# Booster_Board.net
KiCad netlist of a schematic drawn in Altium Designer
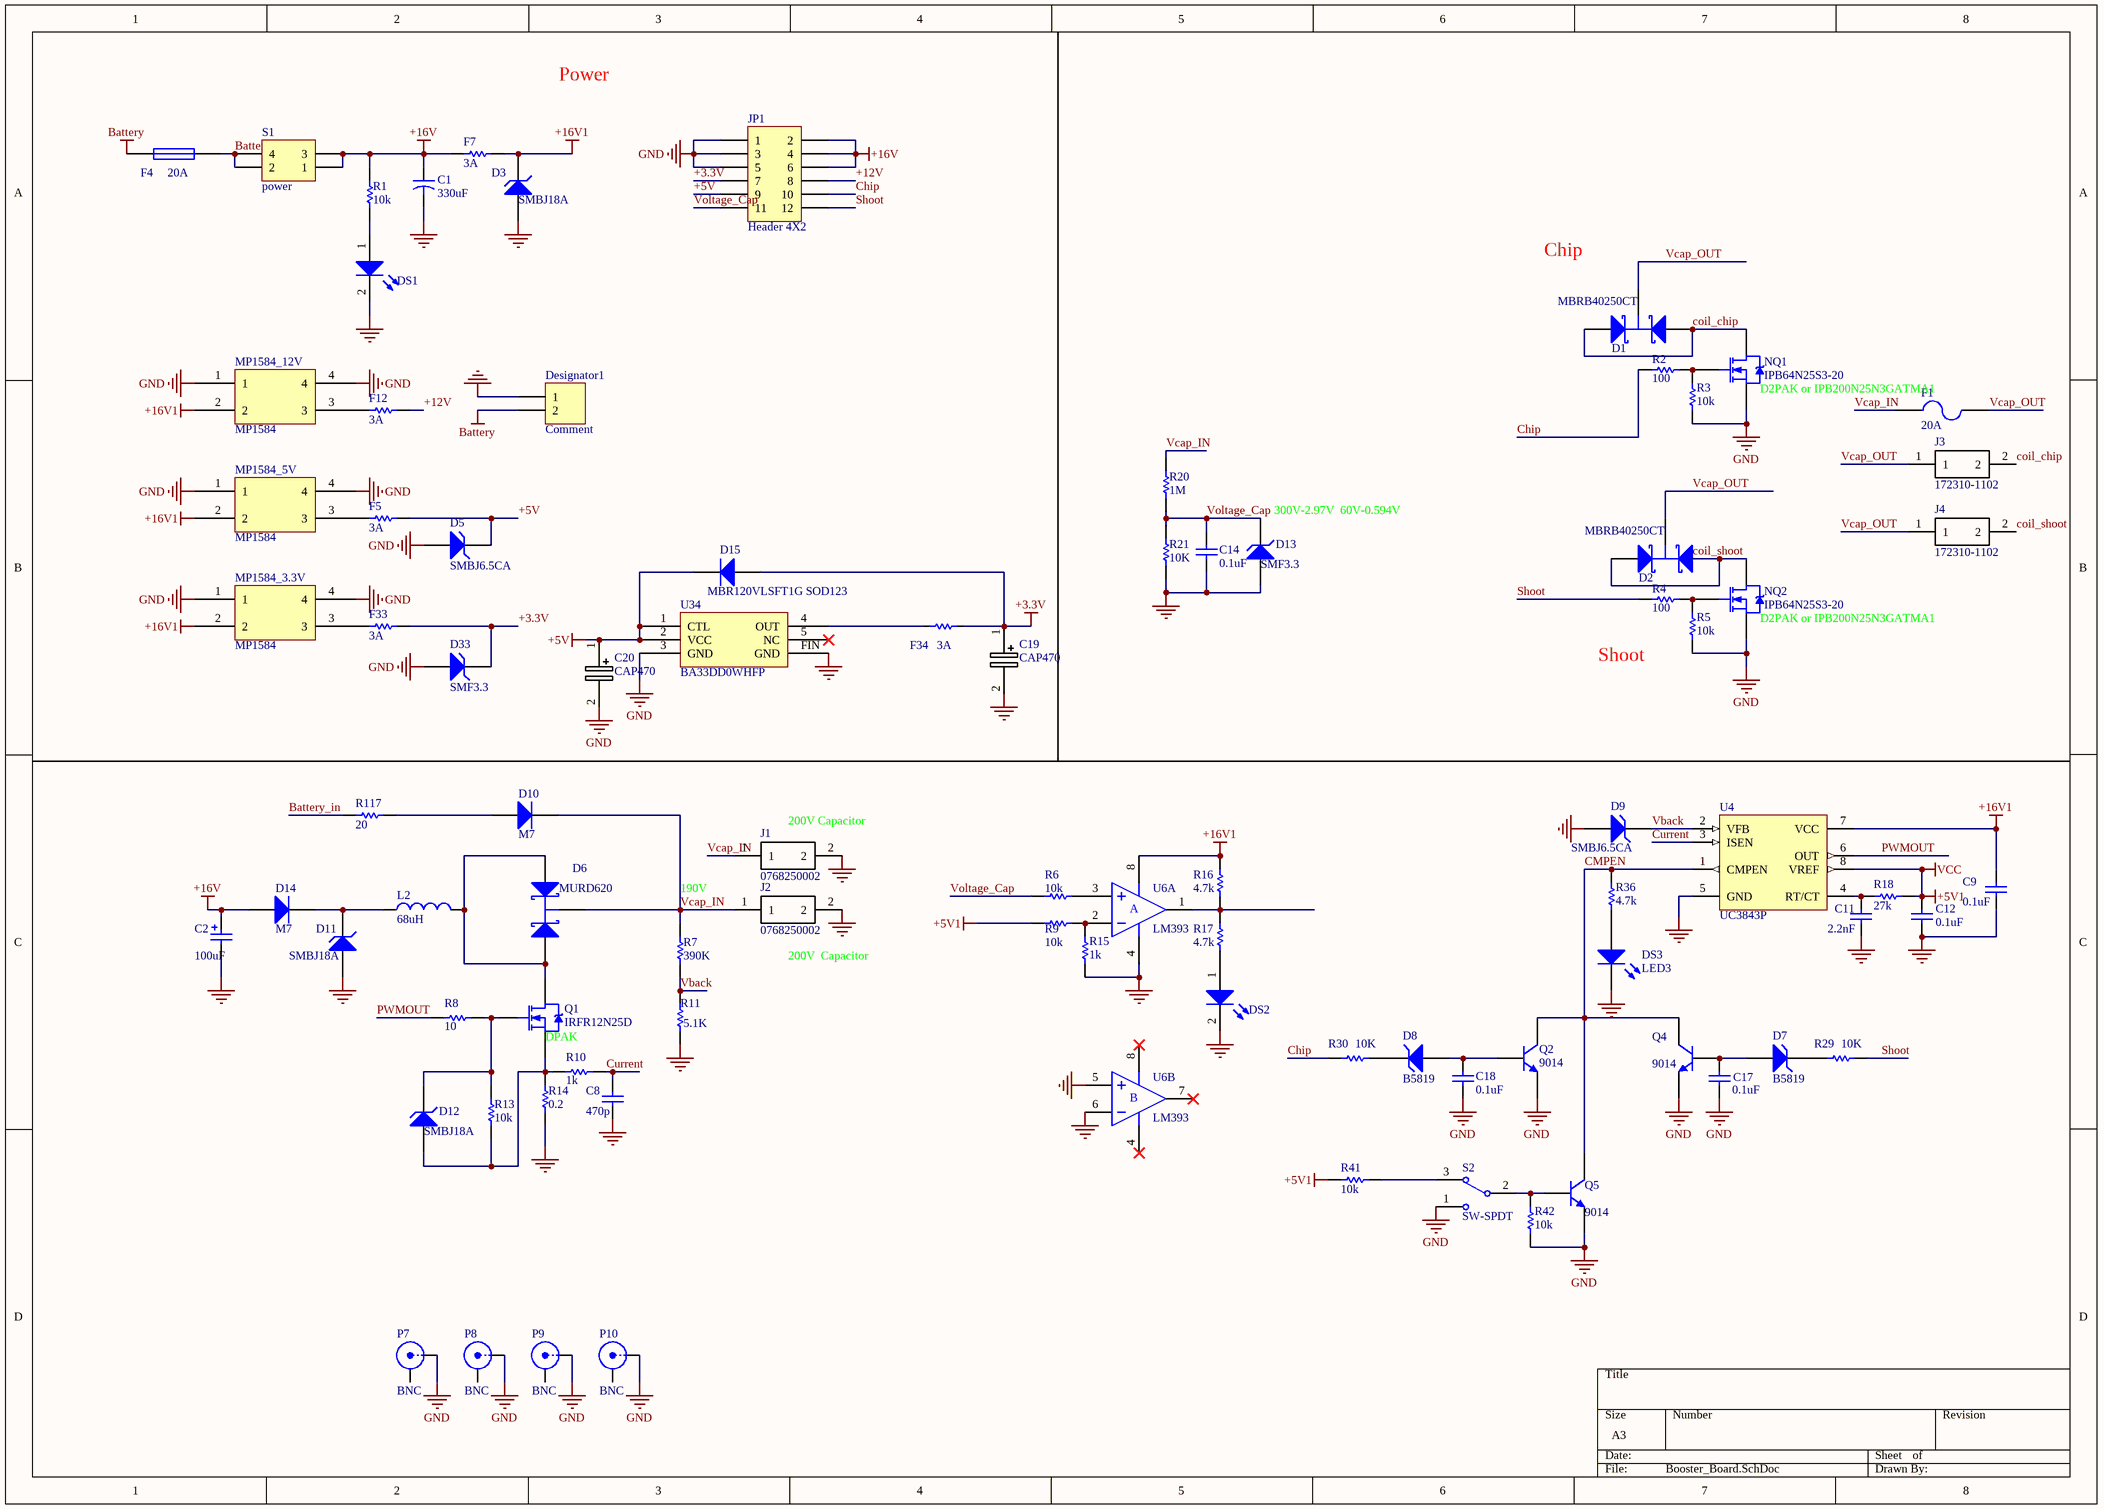
[diagram p0: Booster_Board.SchDoc]

(export (version "E")
  (design (tool "Eeschema 10.0.6"))
  (components
    (comp (ref "C1")
      (value "330uF")
      (footprint "470uF")
      (description "Capacitor")
      (fields (field (name "PUBLISHER") "Altium Limited"))
      (libsource (lib "Miscellaneous Devices") (part "Cap2"))
    )
    (comp (ref "C2")
      (value "100uF")
      (footprint "100uF")
      (description "Polarized Capacitor (Radial)")
      (fields
        (field (name "MANUFACTURER") "Generic Components")
        (field (name "Comment") "100uf")
        (field (name "PUBLISHER") "Altium Hobart Technology Centre")
      )
      (libsource (lib "Miscellaneous Devices") (part "Cap Pol1"))
    )
    (comp (ref "C8")
      (value "470p")
      (footprint "0805C")
      (description "Capacitor")
      (fields
        (field (name "MANUFACTURER") "Generic Components")
        (field (name "PUBLISHER") "Altium Hobart Technology Centre")
      )
      (libsource (lib "Miscellaneous Devices") (part "Cap"))
    )
    (comp (ref "C9")
      (value "0.1uF")
      (footprint "0805C")
      (description "Capacitor")
      (fields (field (name "PUBLISHER") "Altium Limited"))
      (libsource (lib "Miscellaneous Devices") (part "Cap"))
    )
    (comp (ref "C11")
      (value "2.2nF")
      (footprint "0805C")
      (description "Capacitor")
      (fields
        (field (name "MANUFACTURER") "Generic Components")
        (field (name "Comment") "2.2nf")
        (field (name "PUBLISHER") "Altium Hobart Technology Centre")
      )
      (libsource (lib "Miscellaneous Devices") (part "Cap"))
    )
    (comp (ref "C12")
      (value "0.1uF")
      (footprint "0805C")
      (description "Capacitor")
      (fields
        (field (name "MANUFACTURER") "Generic Components")
        (field (name "PUBLISHER") "Altium Hobart Technology Centre")
      )
      (libsource (lib "Miscellaneous Devices") (part "Cap"))
    )
    (comp (ref "C14")
      (value "0.1uF")
      (footprint "0805C")
      (description "Capacitor")
      (fields (field (name "PUBLISHER") "Altium Limited"))
      (libsource (lib "Miscellaneous Devices") (part "Cap"))
    )
    (comp (ref "C17")
      (value "0.1uF")
      (footprint "0805c")
      (description "Capacitor")
      (fields (field (name "PUBLISHER") "Altium Limited"))
      (libsource (lib "Miscellaneous Devices") (part "Cap"))
    )
    (comp (ref "C18")
      (value "0.1uF")
      (footprint "0805c")
      (description "Capacitor")
      (fields (field (name "PUBLISHER") "Altium Limited"))
      (libsource (lib "Miscellaneous Devices") (part "Cap"))
    )
    (comp (ref "C19")
      (value "CAP470")
      (footprint "Main_Board:CAPPM7360X200N")
      (description "470uF电容贴片")
      (fields
        (field (name "MANUFACTURER_PART_NUMBER") "T523H477M016APE0707280")
        (field (name "MOUSER PART NUMBER") "80-T523H477M16P070LR")
      )
      (libsource (lib "Main_Board") (part "T523H477M016APE0707280"))
    )
    (comp (ref "C20")
      (value "CAP470")
      (footprint "Main_Board:CAPPM7360X200N")
      (description "470uF电容贴片")
      (fields
        (field (name "MANUFACTURER_PART_NUMBER") "T523H477M016APE0707280")
        (field (name "MOUSER PART NUMBER") "80-T523H477M16P070LR")
      )
      (libsource (lib "Main_Board") (part "T523H477M016APE0707280"))
    )
    (comp (ref "D1")
      (value "MBRB40250CT")
      (footprint "D2PAK")
      (description "Schottky Rectifier")
      (fields
        (field (name "MANUFACTURER") "International Rectifier")
        (field (name "PUBLISHER") "Altium Hobart Technology Centre")
      )
      (libsource (lib "IR Discrete Diode") (part "MBRB1545CT"))
    )
    (comp (ref "D2")
      (value "MBRB40250CT")
      (footprint "D2PAK")
      (description "Schottky Rectifier")
      (fields
        (field (name "MANUFACTURER") "International Rectifier")
        (field (name "PUBLISHER") "Altium Hobart Technology Centre")
      )
      (libsource (lib "IR Discrete Diode") (part "MBRB1545CT"))
    )
    (comp (ref "D3")
      (value "SMBJ18A")
      (footprint "booster:SMBJ6.5")
      (description "Zener Diode")
      (fields (field (name "PUBLISHER") "Altium Limited"))
      (libsource (lib "Miscellaneous Devices") (part "D Zener"))
    )
    (comp (ref "D5")
      (value "SMBJ6.5CA")
      (footprint "SMBJ6.5")
      (description "Zener Diode")
      (fields (field (name "PUBLISHER") "Altium Limited"))
      (libsource (lib "Miscellaneous Devices") (part "D Zener"))
    )
    (comp (ref "D6")
      (value "MURD620")
      (footprint "DPAK")
      (description "Schottky Rectifier")
      (fields
        (field (name "MANUFACTURER") "International Rectifier")
        (field (name "PUBLISHER") "Altium Hobart Technology Centre")
      )
      (libsource (lib "IR Discrete Diode") (part "MBRB1545CT"))
    )
    (comp (ref "D7")
      (value "B5819")
      (footprint "sod-123")
      (description "Zener Diode")
      (fields (field (name "PUBLISHER") "Altium Limited"))
      (libsource (lib "Miscellaneous Devices") (part "D Zener"))
    )
    (comp (ref "D8")
      (value "B5819")
      (footprint "sod-123")
      (description "Zener Diode")
      (fields (field (name "PUBLISHER") "Altium Limited"))
      (libsource (lib "Miscellaneous Devices") (part "D Zener"))
    )
    (comp (ref "D9")
      (value "SMBJ6.5CA")
      (footprint "SMBJ6.5")
      (description "Zener Diode")
      (fields (field (name "PUBLISHER") "Altium Limited"))
      (libsource (lib "Miscellaneous Devices") (part "D Zener"))
    )
    (comp (ref "D10")
      (value "M7")
      (footprint "booster:SMA")
      (description "Default Diode")
      (fields
        (field (name "MANUFACTURER") "Generic Components")
        (field (name "PUBLISHER") "Altium Hobart Technology Centre")
      )
      (libsource (lib "Miscellaneous Devices") (part "Diode"))
    )
    (comp (ref "D11")
      (value "SMBJ18A")
      (footprint "booster:SMBJ6.5")
      (description "Zener Diode")
      (fields (field (name "PUBLISHER") "Altium Limited"))
      (libsource (lib "Miscellaneous Devices") (part "D Zener"))
    )
    (comp (ref "D12")
      (value "SMBJ18A")
      (footprint "SMBJ6.5")
      (description "Zener Diode")
      (fields (field (name "PUBLISHER") "Altium Limited"))
      (libsource (lib "Miscellaneous Devices") (part "D Zener"))
    )
    (comp (ref "D13")
      (value "SMF3.3")
      (footprint "SMF33")
      (description "Zener Diode")
      (fields (field (name "PUBLISHER") "Altium Limited"))
      (libsource (lib "Miscellaneous Devices") (part "D Zener"))
    )
    (comp (ref "D14")
      (value "M7")
      (footprint "booster:SMA")
      (description "Default Diode")
      (fields
        (field (name "MANUFACTURER") "Generic Components")
        (field (name "PUBLISHER") "Altium Hobart Technology Centre")
      )
      (libsource (lib "Miscellaneous Devices") (part "Diode"))
    )
    (comp (ref "D15")
      (value "MBR120VLSFT1G SOD123")
      (footprint "Main_Board:sod123")
      (description "Default Diode")
      (fields
        (field (name "MANUFACTURER") "Generic Components")
        (field (name "PUBLISHER") "Altium Hobart Technology Centre")
      )
      (libsource (lib "Miscellaneous Devices") (part "Diode"))
    )
    (comp (ref "D33")
      (value "SMF3.3")
      (footprint "SMF33")
      (description "Zener Diode")
      (fields (field (name "PUBLISHER") "Altium Limited"))
      (libsource (lib "Miscellaneous Devices") (part "D Zener"))
    )
    (comp (ref "Designator1")
      (value "Comment")
      (footprint "XT60PW")
      (description "Header, 2-Pin")
      (fields (field (name "PUBLISHER") "Altium Limited"))
      (libsource (lib "Miscellaneous Connectors") (part "Header 2"))
    )
    (comp (ref "DS1")
      (value "LED2")
      (footprint "0805A")
      (description "Typical RED, GREEN, YELLOW, AMBER GaAs LED")
      (fields
        (field (name "MANUFACTURER") "Generic Components")
        (field (name "PUBLISHER") "Altium Hobart Technology Centre")
      )
      (libsource (lib "") (part "LED2_1"))
    )
    (comp (ref "DS2")
      (value "LED2")
      (footprint "0805A")
      (description "Typical RED, GREEN, YELLOW, AMBER GaAs LED")
      (fields
        (field (name "MANUFACTURER") "Generic Components")
        (field (name "PUBLISHER") "Altium Hobart Technology Centre")
      )
      (libsource (lib "") (part "LED2_1"))
    )
    (comp (ref "DS3")
      (value "LED3")
      (footprint "booster:0805A")
      (description "Typical RED, GREEN, YELLOW, AMBER GaAs LED")
      (fields (field (name "PUBLISHER") "Altium Limited"))
      (libsource (lib "Miscellaneous Devices") (part "LED2"))
    )
    (comp (ref "F1")
      (value "20A")
      (footprint "20A")
      (fields (field (name "PUBLISHER") "Altium Limited"))
      (libsource (lib "Miscellaneous Devices") (part "Fuse 2"))
    )
    (comp (ref "F4")
      (value "20A")
      (footprint "20A")
      (description "Fuse")
      (fields (field (name "PUBLISHER") "Altium Limited"))
      (libsource (lib "Miscellaneous Devices") (part "Fuse 1"))
    )
    (comp (ref "F5")
      (value "3A")
      (footprint "2512r")
      (description "Resistor")
      (fields
        (field (name "MANUFACTURER") "Generic Components")
        (field (name "PUBLISHER") "Altium Hobart Technology Centre")
      )
      (libsource (lib "Miscellaneous Devices") (part "Res1"))
    )
    (comp (ref "F7")
      (value "3A")
      (footprint "2512r")
      (description "Resistor")
      (fields
        (field (name "MANUFACTURER") "Generic Components")
        (field (name "PUBLISHER") "Altium Hobart Technology Centre")
      )
      (libsource (lib "Miscellaneous Devices") (part "Res1"))
    )
    (comp (ref "F12")
      (value "3A")
      (footprint "2512r")
      (description "Resistor")
      (fields
        (field (name "MANUFACTURER") "Generic Components")
        (field (name "PUBLISHER") "Altium Hobart Technology Centre")
      )
      (libsource (lib "Miscellaneous Devices") (part "Res1"))
    )
    (comp (ref "F33")
      (value "3A")
      (footprint "2512r")
      (description "Resistor")
      (fields
        (field (name "MANUFACTURER") "Generic Components")
        (field (name "PUBLISHER") "Altium Hobart Technology Centre")
      )
      (libsource (lib "Miscellaneous Devices") (part "Res1"))
    )
    (comp (ref "F34")
      (value "3A")
      (footprint "2512r")
      (description "Resistor")
      (fields (field (name "PUBLISHER") "Altium Limited"))
      (libsource (lib "") (part "Res1_1"))
    )
    (comp (ref "J1")
      (value "0768250002")
      (footprint "booster:0768250002_version2")
      (description "Connector")
      (libsource (lib "booster") (part "0768250002"))
    )
    (comp (ref "J2")
      (value "0768250002")
      (footprint "booster:0768250002_version2")
      (description "Connector")
      (libsource (lib "booster") (part "0768250002"))
    )
    (comp (ref "J3")
      (value "172310-1102")
      (footprint "booster:172310-1102_VERSION2")
      (description "Connector")
      (fields (field (name "MOUSER PART NUMBER") "538-172310-1102") (field (name "RS PART NUMBER") "8951880"))
      (libsource (lib "booster") (part "172310-1102"))
    )
    (comp (ref "J4")
      (value "172310-1102")
      (footprint "booster:172310-1102_VERSION2")
      (description "Connector")
      (fields (field (name "MOUSER PART NUMBER") "538-172310-1102") (field (name "RS PART NUMBER") "8951880"))
      (libsource (lib "booster") (part "172310-1102"))
    )
    (comp (ref "JP1")
      (value "Header 4X2")
      (footprint "2*6_2.5mm")
      (description "Header, 4-Pin, Dual row")
      (fields (field (name "PUBLISHER") "Altium Limited"))
      (libsource (lib "booster") (part "Header 6X2"))
    )
    (comp (ref "L2")
      (value "68uH")
      (footprint "INDPM120120X1020N")
      (description "Inductor")
      (fields (field (name "PUBLISHER") "Altium Limited"))
      (libsource (lib "Miscellaneous Devices") (part "Inductor"))
    )
    (comp (ref "MP1584_3.3V") (value "MP1584") (footprint "1584") (libsource (lib "booster") (part "MP1584")))
    (comp (ref "MP1584_5V") (value "MP1584") (footprint "1584") (libsource (lib "booster") (part "MP1584")))
    (comp (ref "MP1584_12V") (value "MP1584") (footprint "1584") (libsource (lib "booster") (part "MP1584")))
    (comp (ref "NQ1")
      (value "IPB64N25S3-20")
      (footprint "D2PAK")
      (description "HEXFET Power MOSFET")
      (fields
        (field (name "MANUFACTURER") "International Rectifier")
        (field (name "PUBLISHER") "Altium Hobart Technology Centre")
      )
      (libsource (lib "IR Discrete MOSFET") (part "IRFP460"))
    )
    (comp (ref "NQ2")
      (value "IPB64N25S3-20")
      (footprint "D2PAK")
      (description "HEXFET Power MOSFET")
      (fields
        (field (name "MANUFACTURER") "International Rectifier")
        (field (name "PUBLISHER") "Altium Hobart Technology Centre")
      )
      (libsource (lib "IR Discrete MOSFET") (part "IRFP460"))
    )
    (comp (ref "P7")
      (value "BNC")
      (footprint "hole")
      (description "BNC Elbow Connector")
      (fields (field (name "PUBLISHER") "Altium Limited"))
      (libsource (lib "Miscellaneous Connectors") (part "BNC"))
    )
    (comp (ref "P8")
      (value "BNC")
      (footprint "hole")
      (description "BNC Elbow Connector")
      (fields (field (name "PUBLISHER") "Altium Limited"))
      (libsource (lib "Miscellaneous Connectors") (part "BNC"))
    )
    (comp (ref "P9")
      (value "BNC")
      (footprint "hole")
      (description "BNC Elbow Connector")
      (fields (field (name "PUBLISHER") "Altium Limited"))
      (libsource (lib "Miscellaneous Connectors") (part "BNC"))
    )
    (comp (ref "P10")
      (value "BNC")
      (footprint "hole")
      (description "BNC Elbow Connector")
      (fields (field (name "PUBLISHER") "Altium Limited"))
      (libsource (lib "Miscellaneous Connectors") (part "BNC"))
    )
    (comp (ref "Q1")
      (value "IRFR12N25D")
      (footprint "DPAK")
      (description "N-Channel Power MOSFET")
      (fields (field (name "PUBLISHER") "Altium Limited"))
      (libsource (lib "Miscellaneous Devices") (part "NMOS-2"))
    )
    (comp (ref "Q2")
      (value "9014")
      (footprint "元器件:SOT23A")
      (description "NPN General Purpose Amplifier")
      (fields
        (field (name "MANUFACTURER") "Fairchild Semiconductor")
        (field (name "PUBLISHER") "Altium Hobart Technology Centre")
      )
      (libsource (lib "FSC Discrete BJT") (part "BC817-40"))
    )
    (comp (ref "Q4")
      (value "9014")
      (footprint "sot23a")
      (description "NPN General Purpose Amplifier")
      (fields
        (field (name "MANUFACTURER") "Fairchild Semiconductor")
        (field (name "PUBLISHER") "Altium Hobart Technology Centre")
      )
      (libsource (lib "FSC Discrete BJT") (part "BC817-40"))
    )
    (comp (ref "Q5")
      (value "9014")
      (footprint "SOT23a")
      (description "NPN General Purpose Amplifier")
      (fields
        (field (name "MANUFACTURER") "Fairchild Semiconductor")
        (field (name "PUBLISHER") "Altium Hobart Technology Centre")
      )
      (libsource (lib "FSC Discrete BJT") (part "BC817-40"))
    )
    (comp (ref "R1")
      (value "10k")
      (footprint "0805R")
      (description "Resistor")
      (fields
        (field (name "MANUFACTURER") "Generic Components")
        (field (name "PUBLISHER") "Altium Hobart Technology Centre")
      )
      (libsource (lib "Miscellaneous Devices") (part "Res1"))
    )
    (comp (ref "R2")
      (value "100")
      (footprint "0805r")
      (description "Semiconductor Resistor")
      (fields
        (field (name "MANUFACTURER") "Generic Components")
        (field (name "PUBLISHER") "Altium Hobart Technology Centre")
      )
      (libsource (lib "Miscellaneous Devices") (part "Res Semi"))
    )
    (comp (ref "R3")
      (value "10k")
      (footprint "0805R")
      (description "Semiconductor Resistor")
      (fields
        (field (name "MANUFACTURER") "Generic Components")
        (field (name "PUBLISHER") "Altium Hobart Technology Centre")
      )
      (libsource (lib "Miscellaneous Devices") (part "Res Semi"))
    )
    (comp (ref "R4")
      (value "100")
      (footprint "0805r")
      (description "Semiconductor Resistor")
      (fields
        (field (name "MANUFACTURER") "Generic Components")
        (field (name "PUBLISHER") "Altium Hobart Technology Centre")
      )
      (libsource (lib "Miscellaneous Devices") (part "Res Semi"))
    )
    (comp (ref "R5")
      (value "10k")
      (footprint "0805R")
      (description "Semiconductor Resistor")
      (fields
        (field (name "MANUFACTURER") "Generic Components")
        (field (name "PUBLISHER") "Altium Hobart Technology Centre")
      )
      (libsource (lib "Miscellaneous Devices") (part "Res Semi"))
    )
    (comp (ref "R6")
      (value "10k")
      (footprint "0805R")
      (description "Resistor")
      (fields
        (field (name "MANUFACTURER") "Generic Components")
        (field (name "PUBLISHER") "Altium Hobart Technology Centre")
      )
      (libsource (lib "HAIBAO_MEGAV1.0_1") (part "Res1"))
    )
    (comp (ref "R7")
      (value "390K")
      (footprint "0805R")
      (description "Resistor")
      (fields
        (field (name "MANUFACTURER") "Generic Components")
        (field (name "PUBLISHER") "Altium Hobart Technology Centre")
      )
      (libsource (lib "Miscellaneous Devices") (part "Res1"))
    )
    (comp (ref "R8")
      (value "10")
      (footprint "0805R")
      (description "Resistor")
      (fields
        (field (name "MANUFACTURER") "Generic Components")
        (field (name "PUBLISHER") "Altium Hobart Technology Centre")
      )
      (libsource (lib "Miscellaneous Devices") (part "Res1"))
    )
    (comp (ref "R9")
      (value "10k")
      (footprint "0805R")
      (description "Resistor")
      (fields
        (field (name "MANUFACTURER") "Generic Components")
        (field (name "PUBLISHER") "Altium Hobart Technology Centre")
      )
      (libsource (lib "HAIBAO_MEGAV1.0_1") (part "Res1"))
    )
    (comp (ref "R10")
      (value "1k")
      (footprint "0805R")
      (description "Resistor")
      (fields
        (field (name "MANUFACTURER") "Generic Components")
        (field (name "PUBLISHER") "Altium Hobart Technology Centre")
      )
      (libsource (lib "Miscellaneous Devices") (part "Res1"))
    )
    (comp (ref "R11")
      (value "5.1K")
      (footprint "0805R")
      (description "Resistor")
      (fields
        (field (name "MANUFACTURER") "Generic Components")
        (field (name "Comment") "3.3K")
        (field (name "PUBLISHER") "Altium Hobart Technology Centre")
      )
      (libsource (lib "Miscellaneous Devices") (part "Res1"))
    )
    (comp (ref "R13")
      (value "10k")
      (footprint "0805R")
      (description "Resistor")
      (fields
        (field (name "MANUFACTURER") "Generic Components")
        (field (name "PUBLISHER") "Altium Hobart Technology Centre")
      )
      (libsource (lib "Miscellaneous Devices") (part "Res1"))
    )
    (comp (ref "R14")
      (value "0.2")
      (footprint "0.2_4527R")
      (description "Resistor")
      (fields
        (field (name "MANUFACTURER") "Generic Components")
        (field (name "PUBLISHER") "Altium Hobart Technology Centre")
      )
      (libsource (lib "Miscellaneous Devices") (part "Res1"))
    )
    (comp (ref "R15")
      (value "1k")
      (footprint "0805R")
      (description "Resistor")
      (fields
        (field (name "MANUFACTURER") "Generic Components")
        (field (name "PUBLISHER") "Altium Hobart Technology Centre")
      )
      (libsource (lib "HAIBAO_MEGAV1.0_1") (part "Res1"))
    )
    (comp (ref "R16")
      (value "4.7k")
      (footprint "0805R")
      (description "Resistor")
      (fields
        (field (name "MANUFACTURER") "Generic Components")
        (field (name "PUBLISHER") "Altium Hobart Technology Centre")
      )
      (libsource (lib "HAIBAO_MEGAV1.0_1") (part "Res1"))
    )
    (comp (ref "R17")
      (value "4.7k")
      (footprint "0805R")
      (description "Resistor")
      (fields
        (field (name "MANUFACTURER") "Generic Components")
        (field (name "PUBLISHER") "Altium Hobart Technology Centre")
      )
      (libsource (lib "HAIBAO_MEGAV1.0_1") (part "Res1"))
    )
    (comp (ref "R18")
      (value "27k")
      (footprint "0805R")
      (description "Resistor")
      (fields
        (field (name "MANUFACTURER") "Generic Components")
        (field (name "PUBLISHER") "Altium Hobart Technology Centre")
      )
      (libsource (lib "Miscellaneous Devices") (part "Res1"))
    )
    (comp (ref "R20")
      (value "1M")
      (footprint "0805R")
      (description "Resistor")
      (fields
        (field (name "MANUFACTURER") "Generic Components")
        (field (name "Comment") "1m")
        (field (name "PUBLISHER") "Altium Hobart Technology Centre")
      )
      (libsource (lib "Miscellaneous Devices") (part "Res1"))
    )
    (comp (ref "R21")
      (value "10K")
      (footprint "0805R")
      (description "Resistor")
      (fields
        (field (name "MANUFACTURER") "Generic Components")
        (field (name "Comment") "10k")
        (field (name "PUBLISHER") "Altium Hobart Technology Centre")
      )
      (libsource (lib "Miscellaneous Devices") (part "Res1"))
    )
    (comp (ref "R29")
      (value "10K")
      (footprint "0805r")
      (description "Resistor")
      (fields
        (field (name "MANUFACTURER") "Generic Components")
        (field (name "Comment") "10k")
        (field (name "PUBLISHER") "Altium Hobart Technology Centre")
      )
      (libsource (lib "Miscellaneous Devices") (part "Res1"))
    )
    (comp (ref "R30")
      (value "10K")
      (footprint "0805r")
      (description "Resistor")
      (fields
        (field (name "MANUFACTURER") "Generic Components")
        (field (name "Comment") "10k")
        (field (name "PUBLISHER") "Altium Hobart Technology Centre")
      )
      (libsource (lib "Miscellaneous Devices") (part "Res1"))
    )
    (comp (ref "R36")
      (value "4.7k")
      (footprint "0805r")
      (description "Resistor")
      (fields
        (field (name "MANUFACTURER") "Generic Components")
        (field (name "PUBLISHER") "Altium Hobart Technology Centre")
      )
      (libsource (lib "Miscellaneous Devices") (part "Res1"))
    )
    (comp (ref "R41")
      (value "10k")
      (footprint "0805r")
      (description "Resistor")
      (fields
        (field (name "MANUFACTURER") "Generic Components")
        (field (name "PUBLISHER") "Altium Hobart Technology Centre")
      )
      (libsource (lib "Miscellaneous Devices") (part "Res1"))
    )
    (comp (ref "R42")
      (value "10k")
      (footprint "0805r")
      (description "Resistor")
      (fields
        (field (name "MANUFACTURER") "Generic Components")
        (field (name "PUBLISHER") "Altium Hobart Technology Centre")
      )
      (libsource (lib "Miscellaneous Devices") (part "Res1"))
    )
    (comp (ref "R117")
      (value "20")
      (footprint "20_2512r")
      (description "Resistor")
      (fields
        (field (name "MANUFACTURER") "Generic Components")
        (field (name "PUBLISHER") "Altium Hobart Technology Centre")
      )
      (libsource (lib "Miscellaneous Devices") (part "Res1"))
    )
    (comp (ref "S1")
      (value "power")
      (footprint "Rocker_Switch")
      (description "Header, 2-Pin, Dual row")
      (fields (field (name "PUBLISHER") "Altium Limited"))
      (libsource (lib "Miscellaneous Connectors") (part "Header 2X2"))
    )
    (comp (ref "S2")
      (value "SW-SPDT")
      (footprint "SMALL_switch")
      (description "SPDT Subminiature Toggle Switch, Right Angle Mounting, Vertical Actuation")
      (fields (field (name "PUBLISHER") "Altium Limited"))
      (libsource (lib "Miscellaneous Devices") (part "SW-SPDT"))
    )
    (comp (ref "U4")
      (value "UC3843P")
      (footprint "SO-G8")
      (description "Current-Mode PWM Controller")
      (fields (field (name "PUBLISHER") "Altium Limited"))
      (libsource (lib "TI Power Mgt DC-DC Converter") (part "UC3843P"))
    )
    (comp (ref "U6")
      (value "LM393")
      (footprint "LM393_SO-G8")
      (libsource (lib "HAIBAO_MEGAV1.0_1") (part "LM393"))
    )
    (comp (ref "U34")
      (value "BA33DD0WHFP")
      (footprint "Main_Board:HRP5_16TO5")
      (libsource (lib "Main_Board") (part "HRP5-16TO5"))
    )
  )
  (nets
    (net (code "1") (name "+3.3V") (class "Default")
      (node (ref "C19") (pin "1") (pinfunction "+_1") (pintype "passive"))
      (node (ref "D15") (pin "1") (pinfunction "A_1") (pintype "passive"))
      (node (ref "D33") (pin "2") (pinfunction "K_2") (pintype "passive"))
      (node (ref "F33") (pin "1") (pinfunction "1_1") (pintype "passive"))
      (node (ref "F34") (pin "2") (pinfunction "2_2") (pintype "passive"))
      (node (ref "JP1") (pin "7") (pinfunction "7_7") (pintype "passive"))
    )
    (net (code "2") (name "+5V") (class "Default")
      (node (ref "C20") (pin "1") (pinfunction "+_1") (pintype "passive"))
      (node (ref "D15") (pin "2") (pinfunction "K_2") (pintype "passive"))
      (node (ref "D5") (pin "2") (pinfunction "K_2") (pintype "passive"))
      (node (ref "F5") (pin "1") (pinfunction "1_1") (pintype "passive"))
      (node (ref "JP1") (pin "9") (pinfunction "9_9") (pintype "passive"))
      (node (ref "U34") (pin "1") (pinfunction "CTL_1") (pintype "passive"))
      (node (ref "U34") (pin "2") (pinfunction "VCC_2") (pintype "passive"))
    )
    (net (code "3") (name "+5V1") (class "Default")
      (node (ref "C12") (pin "1") (pinfunction "1_1") (pintype "passive"))
      (node (ref "R18") (pin "2") (pinfunction "2_2") (pintype "passive"))
      (node (ref "R41") (pin "2") (pinfunction "2_2") (pintype "passive"))
      (node (ref "R9") (pin "2") (pinfunction "2_2") (pintype "passive"))
      (node (ref "U4") (pin "8") (pinfunction "VREF_8") (pintype "output"))
    )
    (net (code "4") (name "+16V") (class "Default")
      (node (ref "C1") (pin "1") (pinfunction "1_1") (pintype "passive"))
      (node (ref "C2") (pin "1") (pinfunction "1_1") (pintype "passive"))
      (node (ref "D14") (pin "1") (pinfunction "A_1") (pintype "passive"))
      (node (ref "F7") (pin "2") (pinfunction "2_2") (pintype "passive"))
      (node (ref "JP1") (pin "2") (pinfunction "2_2") (pintype "passive"))
      (node (ref "JP1") (pin "4") (pinfunction "4_4") (pintype "passive"))
      (node (ref "JP1") (pin "6") (pinfunction "6_6") (pintype "passive"))
      (node (ref "R1") (pin "2") (pinfunction "2_2") (pintype "passive"))
      (node (ref "S1") (pin "1") (pinfunction "1_1") (pintype "passive"))
      (node (ref "S1") (pin "3") (pinfunction "3_3") (pintype "passive"))
    )
    (net (code "5") (name "+16V1") (class "Default")
      (node (ref "C9") (pin "2") (pinfunction "2_2") (pintype "passive"))
      (node (ref "D3") (pin "2") (pinfunction "K_2") (pintype "passive"))
      (node (ref "F7") (pin "1") (pinfunction "1_1") (pintype "passive"))
      (node (ref "MP1584_12V") (pin "2") (pinfunction "2_2") (pintype "passive"))
      (node (ref "MP1584_3.3V") (pin "2") (pinfunction "2_2") (pintype "passive"))
      (node (ref "MP1584_5V") (pin "2") (pinfunction "2_2") (pintype "passive"))
      (node (ref "R16") (pin "2") (pinfunction "2_2") (pintype "passive"))
      (node (ref "U4") (pin "7") (pinfunction "VCC_7") (pintype "power_in"))
      (node (ref "U6") (pin "8") (pinfunction "V+_8") (pintype "power_in"))
    )
    (net (code "6") (name "/+12V") (class "Default")
      (node (ref "F12") (pin "1") (pinfunction "1_1") (pintype "passive"))
      (node (ref "JP1") (pin "8") (pinfunction "8_8") (pintype "passive"))
    )
    (net (code "7") (name "/Battery_in") (class "Default")
      (node (ref "F4") (pin "1") (pinfunction "1_1") (pintype "passive"))
      (node (ref "R117") (pin "2") (pinfunction "2_2") (pintype "passive"))
      (node (ref "S1") (pin "2") (pinfunction "2_2") (pintype "passive"))
      (node (ref "S1") (pin "4") (pinfunction "4_4") (pintype "passive"))
    )
    (net (code "8") (name "/CMPEN") (class "Default")
      (node (ref "Q2") (pin "3") (pinfunction "C_3") (pintype "passive"))
      (node (ref "Q4") (pin "3") (pinfunction "C_3") (pintype "passive"))
      (node (ref "Q5") (pin "3") (pinfunction "C_3") (pintype "passive"))
      (node (ref "R36") (pin "2") (pinfunction "2_2") (pintype "passive"))
      (node (ref "U4") (pin "1") (pinfunction "CMPEN_1") (pintype "output"))
    )
    (net (code "9") (name "/Chip") (class "Default")
      (node (ref "JP1") (pin "10") (pinfunction "10_10") (pintype "passive"))
      (node (ref "R2") (pin "1") (pinfunction "1_1") (pintype "passive"))
      (node (ref "R30") (pin "1") (pinfunction "1_1") (pintype "passive"))
    )
    (net (code "10") (name "/Current") (class "Default")
      (node (ref "C8") (pin "1") (pinfunction "1_1") (pintype "passive"))
      (node (ref "R10") (pin "2") (pinfunction "2_2") (pintype "passive"))
      (node (ref "U4") (pin "3") (pinfunction "ISEN_3") (pintype "input"))
    )
    (net (code "11") (name "/PWMOUT") (class "Default")
      (node (ref "R8") (pin "1") (pinfunction "1_1") (pintype "passive"))
      (node (ref "U4") (pin "6") (pinfunction "OUT_6") (pintype "output"))
    )
    (net (code "12") (name "/Shoot") (class "Default")
      (node (ref "JP1") (pin "12") (pinfunction "12_12") (pintype "passive"))
      (node (ref "R29") (pin "2") (pinfunction "2_2") (pintype "passive"))
      (node (ref "R4") (pin "1") (pinfunction "1_1") (pintype "passive"))
    )
    (net (code "13") (name "/Vback") (class "Default")
      (node (ref "D9") (pin "2") (pinfunction "K_2") (pintype "passive"))
      (node (ref "R11") (pin "2") (pinfunction "2_2") (pintype "passive"))
      (node (ref "R7") (pin "1") (pinfunction "1_1") (pintype "passive"))
      (node (ref "U4") (pin "2") (pinfunction "VFB_2") (pintype "input"))
    )
    (net (code "14") (name "/Vcap_IN") (class "Default")
      (node (ref "D10") (pin "2") (pinfunction "K_2") (pintype "passive"))
      (node (ref "D6") (pin "2") (pinfunction "K_2") (pintype "passive"))
      (node (ref "F1") (pin "1") (pinfunction "1_1") (pintype "passive"))
      (node (ref "J1") (pin "1") (pinfunction "1_1") (pintype "passive"))
      (node (ref "J2") (pin "1") (pinfunction "1_1") (pintype "passive"))
      (node (ref "R20") (pin "2") (pinfunction "2_2") (pintype "passive"))
      (node (ref "R7") (pin "2") (pinfunction "2_2") (pintype "passive"))
    )
    (net (code "15") (name "/Vcap_OUT") (class "Default")
      (node (ref "D1") (pin "2") (pinfunction "K_2") (pintype "passive"))
      (node (ref "D2") (pin "2") (pinfunction "K_2") (pintype "passive"))
      (node (ref "F1") (pin "2") (pinfunction "2_2") (pintype "passive"))
      (node (ref "J3") (pin "1") (pinfunction "1_1") (pintype "passive"))
      (node (ref "J4") (pin "1") (pinfunction "1_1") (pintype "passive"))
    )
    (net (code "16") (name "/Voltage_Cap") (class "Default")
      (node (ref "C14") (pin "2") (pinfunction "2_2") (pintype "passive"))
      (node (ref "D13") (pin "2") (pinfunction "K_2") (pintype "passive"))
      (node (ref "JP1") (pin "11") (pinfunction "11_11") (pintype "passive"))
      (node (ref "R20") (pin "1") (pinfunction "1_1") (pintype "passive"))
      (node (ref "R21") (pin "2") (pinfunction "2_2") (pintype "passive"))
      (node (ref "R6") (pin "2") (pinfunction "2_2") (pintype "passive"))
    )
    (net (code "17") (name "/coil_chip") (class "Default")
      (node (ref "D1") (pin "1") (pinfunction "A1_1") (pintype "passive"))
      (node (ref "D1") (pin "3") (pinfunction "A2_3") (pintype "passive"))
      (node (ref "J3") (pin "2") (pinfunction "2_2") (pintype "passive"))
      (node (ref "NQ1") (pin "2") (pinfunction "D_2") (pintype "passive"))
    )
    (net (code "18") (name "/coil_shoot") (class "Default")
      (node (ref "D2") (pin "1") (pinfunction "A1_1") (pintype "passive"))
      (node (ref "D2") (pin "3") (pinfunction "A2_3") (pintype "passive"))
      (node (ref "J4") (pin "2") (pinfunction "2_2") (pintype "passive"))
      (node (ref "NQ2") (pin "2") (pinfunction "D_2") (pintype "passive"))
    )
    (net (code "19") (name "Battery") (class "Default")
      (node (ref "Designator1") (pin "2") (pinfunction "2_2") (pintype "passive"))
      (node (ref "F4") (pin "2") (pinfunction "2_2") (pintype "passive"))
    )
    (net (code "20") (name "GND") (class "Default")
      (node (ref "C1") (pin "2") (pinfunction "2_2") (pintype "passive"))
      (node (ref "C11") (pin "2") (pinfunction "2_2") (pintype "passive"))
      (node (ref "C12") (pin "2") (pinfunction "2_2") (pintype "passive"))
      (node (ref "C14") (pin "1") (pinfunction "1_1") (pintype "passive"))
      (node (ref "C17") (pin "1") (pinfunction "1_1") (pintype "passive"))
      (node (ref "C18") (pin "1") (pinfunction "1_1") (pintype "passive"))
      (node (ref "C19") (pin "2") (pinfunction "-_2") (pintype "passive"))
      (node (ref "C2") (pin "2") (pinfunction "2_2") (pintype "passive"))
      (node (ref "C20") (pin "2") (pinfunction "-_2") (pintype "passive"))
      (node (ref "C8") (pin "2") (pinfunction "2_2") (pintype "passive"))
      (node (ref "C9") (pin "1") (pinfunction "1_1") (pintype "passive"))
      (node (ref "D11") (pin "1") (pinfunction "A_1") (pintype "passive"))
      (node (ref "D13") (pin "1") (pinfunction "A_1") (pintype "passive"))
      (node (ref "D3") (pin "1") (pinfunction "A_1") (pintype "passive"))
      (node (ref "D33") (pin "1") (pinfunction "A_1") (pintype "passive"))
      (node (ref "D5") (pin "1") (pinfunction "A_1") (pintype "passive"))
      (node (ref "D9") (pin "1") (pinfunction "A_1") (pintype "passive"))
      (node (ref "DS1") (pin "2") (pinfunction "K_2") (pintype "passive"))
      (node (ref "DS2") (pin "2") (pinfunction "K_2") (pintype "passive"))
      (node (ref "DS3") (pin "2") (pinfunction "K_2") (pintype "passive"))
      (node (ref "Designator1") (pin "1") (pinfunction "1_1") (pintype "passive"))
      (node (ref "J1") (pin "2") (pinfunction "2_2") (pintype "passive"))
      (node (ref "J2") (pin "2") (pinfunction "2_2") (pintype "passive"))
      (node (ref "JP1") (pin "1") (pinfunction "1_1") (pintype "passive"))
      (node (ref "JP1") (pin "3") (pinfunction "3_3") (pintype "passive"))
      (node (ref "JP1") (pin "5") (pinfunction "5_5") (pintype "passive"))
      (node (ref "MP1584_12V") (pin "1") (pinfunction "1_1") (pintype "passive"))
      (node (ref "MP1584_12V") (pin "4") (pinfunction "4_4") (pintype "passive"))
      (node (ref "MP1584_3.3V") (pin "1") (pinfunction "1_1") (pintype "passive"))
      (node (ref "MP1584_3.3V") (pin "4") (pinfunction "4_4") (pintype "passive"))
      (node (ref "MP1584_5V") (pin "1") (pinfunction "1_1") (pintype "passive"))
      (node (ref "MP1584_5V") (pin "4") (pinfunction "4_4") (pintype "passive"))
      (node (ref "NQ1") (pin "3") (pinfunction "S_3") (pintype "passive"))
      (node (ref "NQ2") (pin "3") (pinfunction "S_3") (pintype "passive"))
      (node (ref "P10") (pin "1") (pinfunction "X_1") (pintype "passive"))
      (node (ref "P7") (pin "1") (pinfunction "X_1") (pintype "passive"))
      (node (ref "P8") (pin "1") (pinfunction "X_1") (pintype "passive"))
      (node (ref "P9") (pin "1") (pinfunction "X_1") (pintype "passive"))
      (node (ref "Q2") (pin "2") (pinfunction "E_2") (pintype "passive"))
      (node (ref "Q4") (pin "2") (pinfunction "E_2") (pintype "passive"))
      (node (ref "Q5") (pin "2") (pinfunction "E_2") (pintype "passive"))
      (node (ref "R11") (pin "1") (pinfunction "1_1") (pintype "passive"))
      (node (ref "R14") (pin "1") (pinfunction "1_1") (pintype "passive"))
      (node (ref "R15") (pin "2") (pinfunction "2_2") (pintype "passive"))
      (node (ref "R21") (pin "1") (pinfunction "1_1") (pintype "passive"))
      (node (ref "R3") (pin "1") (pinfunction "1_1") (pintype "passive"))
      (node (ref "R42") (pin "2") (pinfunction "2_2") (pintype "passive"))
      (node (ref "R5") (pin "1") (pinfunction "1_1") (pintype "passive"))
      (node (ref "S2") (pin "1") (pinfunction "1_1") (pintype "passive"))
      (node (ref "U34") (pin "3") (pinfunction "GND_3") (pintype "passive"))
      (node (ref "U34") (pin "FIN") (pinfunction "GND_FIN") (pintype "passive"))
      (node (ref "U4") (pin "5") (pinfunction "GND_5") (pintype "power_in"))
      (node (ref "U6") (pin "4") (pinfunction "V-_4") (pintype "power_in"))
      (node (ref "U6") (pin "5") (pinfunction "IN+_5") (pintype "power_in"))
      (node (ref "U6") (pin "6") (pinfunction "IN-_6") (pintype "power_in"))
    )
    (net (code "21") (name "Net-(D6-A1)") (class "Default")
      (node (ref "D6") (pin "1") (pinfunction "A1_1") (pintype "passive"))
      (node (ref "D6") (pin "3") (pinfunction "A2_3") (pintype "passive"))
      (node (ref "L2") (pin "2") (pinfunction "2_2") (pintype "passive"))
      (node (ref "Q1") (pin "2") (pinfunction "D_2") (pintype "passive"))
    )
    (net (code "22") (name "Net-(D7-A)") (class "Default")
      (node (ref "C17") (pin "2") (pinfunction "2_2") (pintype "passive"))
      (node (ref "D7") (pin "1") (pinfunction "A_1") (pintype "passive"))
      (node (ref "Q4") (pin "1") (pinfunction "B_1") (pintype "passive"))
    )
    (net (code "23") (name "Net-(D7-K)") (class "Default")
      (node (ref "D7") (pin "2") (pinfunction "K_2") (pintype "passive"))
      (node (ref "R29") (pin "1") (pinfunction "1_1") (pintype "passive"))
    )
    (net (code "24") (name "Net-(D8-A)") (class "Default")
      (node (ref "C18") (pin "2") (pinfunction "2_2") (pintype "passive"))
      (node (ref "D8") (pin "1") (pinfunction "A_1") (pintype "passive"))
      (node (ref "Q2") (pin "1") (pinfunction "B_1") (pintype "passive"))
    )
    (net (code "25") (name "Net-(D8-K)") (class "Default")
      (node (ref "D8") (pin "2") (pinfunction "K_2") (pintype "passive"))
      (node (ref "R30") (pin "2") (pinfunction "2_2") (pintype "passive"))
    )
    (net (code "26") (name "Net-(D10-A)") (class "Default")
      (node (ref "D10") (pin "1") (pinfunction "A_1") (pintype "passive"))
      (node (ref "R117") (pin "1") (pinfunction "1_1") (pintype "passive"))
    )
    (net (code "27") (name "Net-(D11-K)") (class "Default")
      (node (ref "D11") (pin "2") (pinfunction "K_2") (pintype "passive"))
      (node (ref "D14") (pin "2") (pinfunction "K_2") (pintype "passive"))
      (node (ref "L2") (pin "1") (pinfunction "1_1") (pintype "passive"))
    )
    (net (code "28") (name "Net-(D12-A)") (class "Default")
      (node (ref "D12") (pin "1") (pinfunction "A_1") (pintype "passive"))
      (node (ref "Q1") (pin "3") (pinfunction "S_3") (pintype "passive"))
      (node (ref "R10") (pin "1") (pinfunction "1_1") (pintype "passive"))
      (node (ref "R13") (pin "1") (pinfunction "1_1") (pintype "passive"))
      (node (ref "R14") (pin "2") (pinfunction "2_2") (pintype "passive"))
    )
    (net (code "29") (name "Net-(D12-K)") (class "Default")
      (node (ref "D12") (pin "2") (pinfunction "K_2") (pintype "passive"))
      (node (ref "Q1") (pin "1") (pinfunction "G_1") (pintype "passive"))
      (node (ref "R13") (pin "2") (pinfunction "2_2") (pintype "passive"))
      (node (ref "R8") (pin "2") (pinfunction "2_2") (pintype "passive"))
    )
    (net (code "30") (name "Net-(DS1-A)") (class "Default")
      (node (ref "DS1") (pin "1") (pinfunction "A_1") (pintype "passive"))
      (node (ref "R1") (pin "1") (pinfunction "1_1") (pintype "passive"))
    )
    (net (code "31") (name "Net-(DS2-A)") (class "Default")
      (node (ref "DS2") (pin "1") (pinfunction "A_1") (pintype "passive"))
      (node (ref "R17") (pin "1") (pinfunction "1_1") (pintype "passive"))
    )
    (net (code "32") (name "Net-(DS3-A)") (class "Default")
      (node (ref "DS3") (pin "1") (pinfunction "A_1") (pintype "passive"))
      (node (ref "R36") (pin "1") (pinfunction "1_1") (pintype "passive"))
    )
    (net (code "33") (name "Net-(F5-Pad2)") (class "Default")
      (node (ref "F5") (pin "2") (pinfunction "2_2") (pintype "passive"))
      (node (ref "MP1584_5V") (pin "3") (pinfunction "3_3") (pintype "passive"))
    )
    (net (code "34") (name "Net-(F12-Pad2)") (class "Default")
      (node (ref "F12") (pin "2") (pinfunction "2_2") (pintype "passive"))
      (node (ref "MP1584_12V") (pin "3") (pinfunction "3_3") (pintype "passive"))
    )
    (net (code "35") (name "Net-(F33-Pad2)") (class "Default")
      (node (ref "F33") (pin "2") (pinfunction "2_2") (pintype "passive"))
      (node (ref "MP1584_3.3V") (pin "3") (pinfunction "3_3") (pintype "passive"))
    )
    (net (code "36") (name "Net-(NQ1-G)") (class "Default")
      (node (ref "NQ1") (pin "1") (pinfunction "G_1") (pintype "passive"))
      (node (ref "R2") (pin "2") (pinfunction "2_2") (pintype "passive"))
      (node (ref "R3") (pin "2") (pinfunction "2_2") (pintype "passive"))
    )
    (net (code "37") (name "Net-(NQ2-G)") (class "Default")
      (node (ref "NQ2") (pin "1") (pinfunction "G_1") (pintype "passive"))
      (node (ref "R4") (pin "2") (pinfunction "2_2") (pintype "passive"))
      (node (ref "R5") (pin "2") (pinfunction "2_2") (pintype "passive"))
    )
    (net (code "38") (name "Net-(Q5-B)") (class "Default")
      (node (ref "Q5") (pin "1") (pinfunction "B_1") (pintype "passive"))
      (node (ref "R42") (pin "1") (pinfunction "1_1") (pintype "passive"))
      (node (ref "S2") (pin "2") (pinfunction "2_2") (pintype "passive"))
    )
    (net (code "39") (name "Net-(R41-Pad1)") (class "Default")
      (node (ref "R41") (pin "1") (pinfunction "1_1") (pintype "passive"))
      (node (ref "S2") (pin "3") (pinfunction "3_3") (pintype "passive"))
    )
    (net (code "40") (name "Net-(U4-RT{slash}CT)") (class "Default")
      (node (ref "C11") (pin "1") (pinfunction "1_1") (pintype "passive"))
      (node (ref "R18") (pin "1") (pinfunction "1_1") (pintype "passive"))
      (node (ref "U4") (pin "4") (pinfunction "RT/CT_4") (pintype "passive"))
    )
    (net (code "41") (name "Net-(U6A-IN+)") (class "Default")
      (node (ref "R6") (pin "1") (pinfunction "1_1") (pintype "passive"))
      (node (ref "U6") (pin "3") (pinfunction "IN+_3") (pintype "power_in"))
    )
    (net (code "42") (name "Net-(U6A-IN-)") (class "Default")
      (node (ref "R15") (pin "1") (pinfunction "1_1") (pintype "passive"))
      (node (ref "R9") (pin "1") (pinfunction "1_1") (pintype "passive"))
      (node (ref "U6") (pin "2") (pinfunction "IN-_2") (pintype "power_in"))
    )
    (net (code "43") (name "Net-(U6A-OUT)") (class "Default")
      (node (ref "R16") (pin "1") (pinfunction "1_1") (pintype "passive"))
      (node (ref "R17") (pin "2") (pinfunction "2_2") (pintype "passive"))
      (node (ref "U6") (pin "1") (pinfunction "OUT_1") (pintype "power_in"))
    )
    (net (code "44") (name "Net-(U34-OUT)") (class "Default")
      (node (ref "F34") (pin "1") (pinfunction "1_1") (pintype "passive"))
      (node (ref "U34") (pin "4") (pinfunction "OUT_4") (pintype "passive"))
    )
    (net (code "45") (name "unconnected-(P7-Y-Pad2)") (class "Default")
      (node (ref "P7") (pin "2") (pinfunction "Y_2") (pintype "passive"))
    )
    (net (code "46") (name "unconnected-(P8-Y-Pad2)") (class "Default")
      (node (ref "P8") (pin "2") (pinfunction "Y_2") (pintype "passive"))
    )
    (net (code "47") (name "unconnected-(P9-Y-Pad2)") (class "Default")
      (node (ref "P9") (pin "2") (pinfunction "Y_2") (pintype "passive"))
    )
    (net (code "48") (name "unconnected-(P10-Y-Pad2)") (class "Default")
      (node (ref "P10") (pin "2") (pinfunction "Y_2") (pintype "passive"))
    )
    (net (code "49") (name "unconnected-(U6B-OUT-Pad7)") (class "Default")
      (node (ref "U6") (pin "7") (pinfunction "OUT_7") (pintype "power_in+no_connect"))
    )
    (net (code "50") (name "unconnected-(U6B-V+-Pad8)") (class "Default")
      (node (ref "U6") (pin "8") (pinfunction "V+_8") (pintype "power_in+no_connect"))
    )
    (net (code "51") (name "unconnected-(U6B-V--Pad4)") (class "Default")
      (node (ref "U6") (pin "4") (pinfunction "V-_4") (pintype "power_in+no_connect"))
    )
    (net (code "52") (name "unconnected-(U34-NC-Pad5)") (class "Default")
      (node (ref "U34") (pin "5") (pinfunction "NC_5") (pintype "passive+no_connect"))
    )
  )
)
